# cpu_eval_board.net
KiCad netlist of a schematic drawn in EAGLE
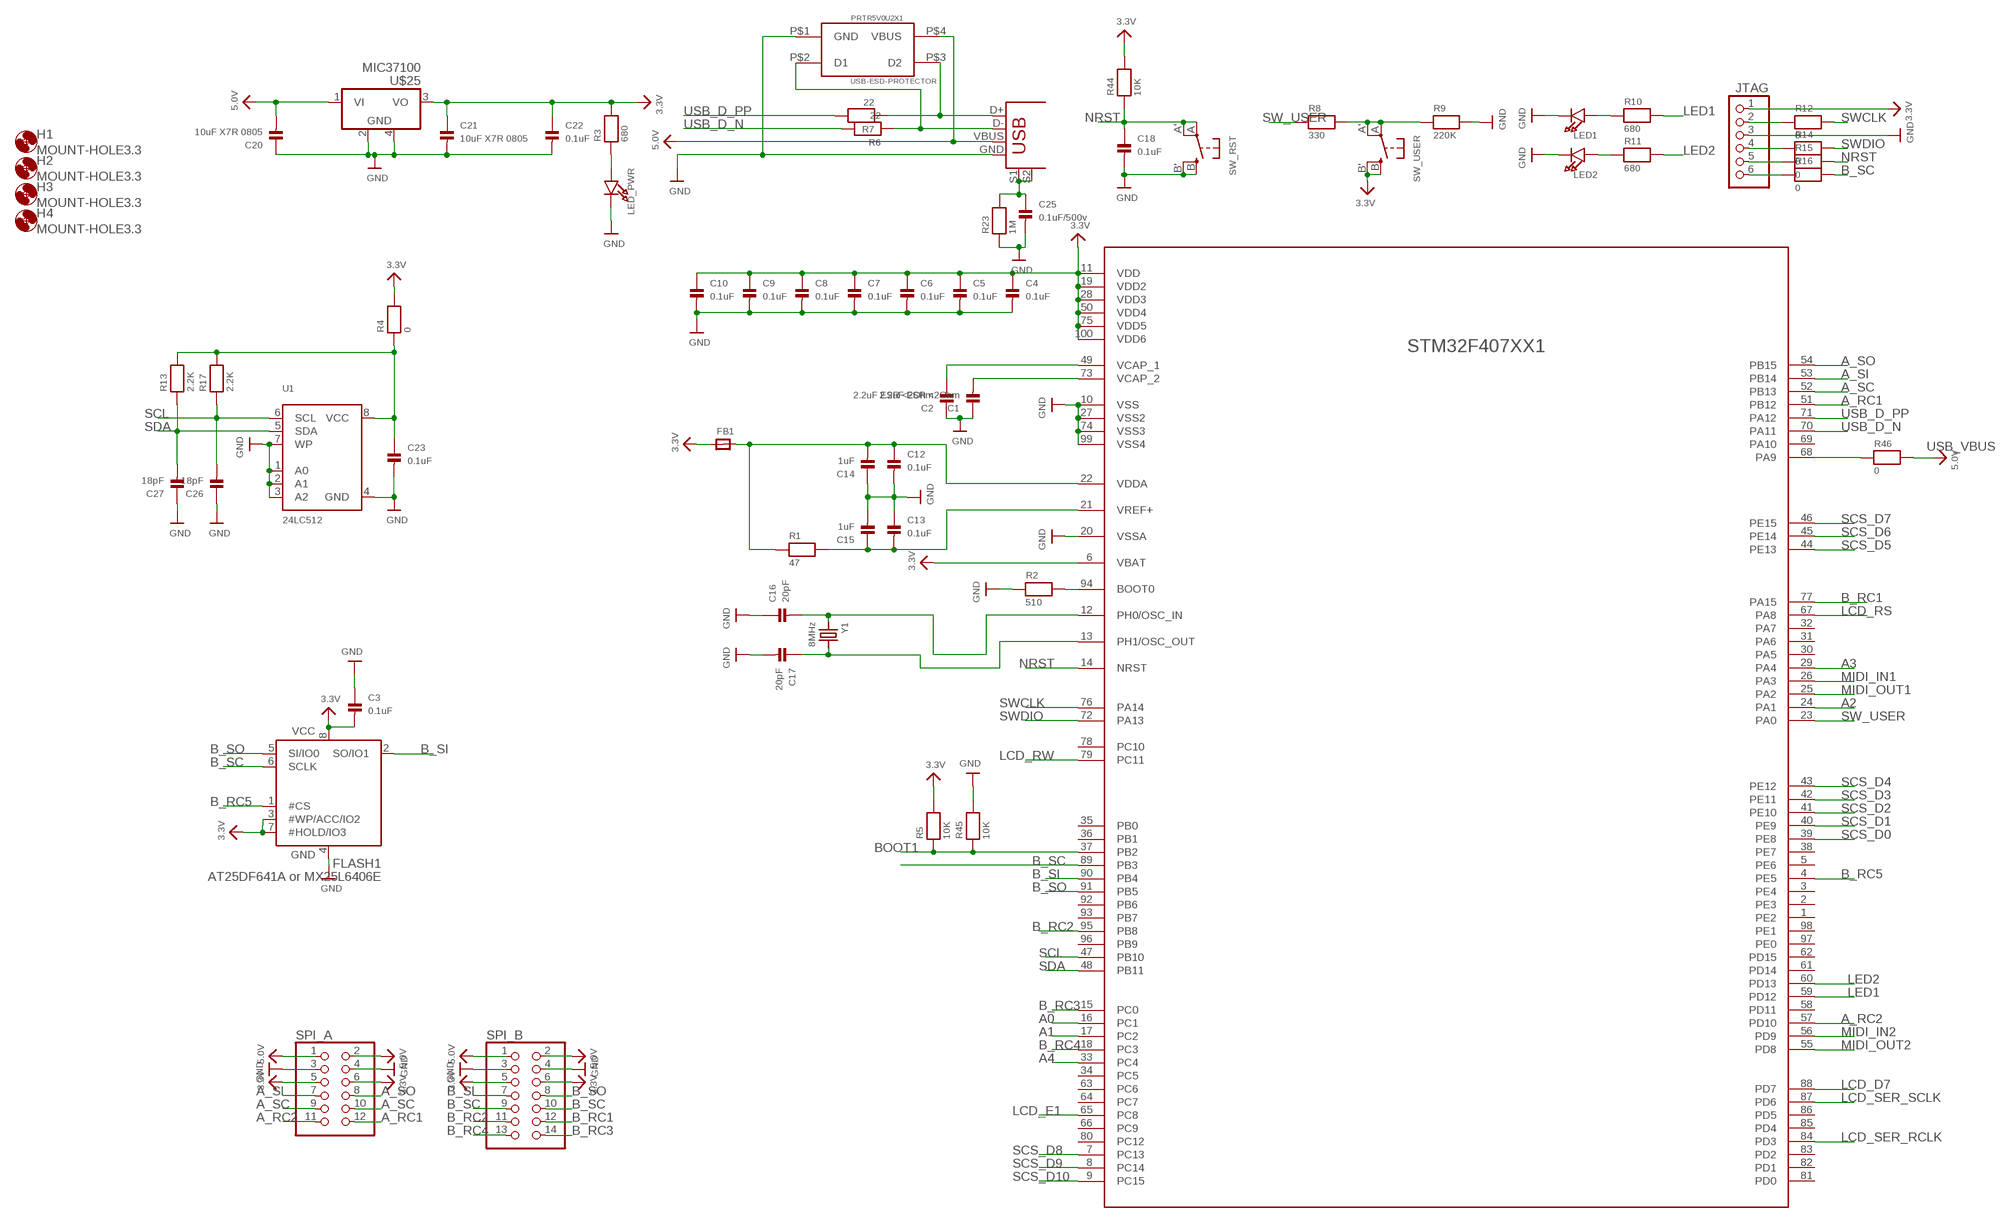
[diagram p0: schematic, sheet 1]
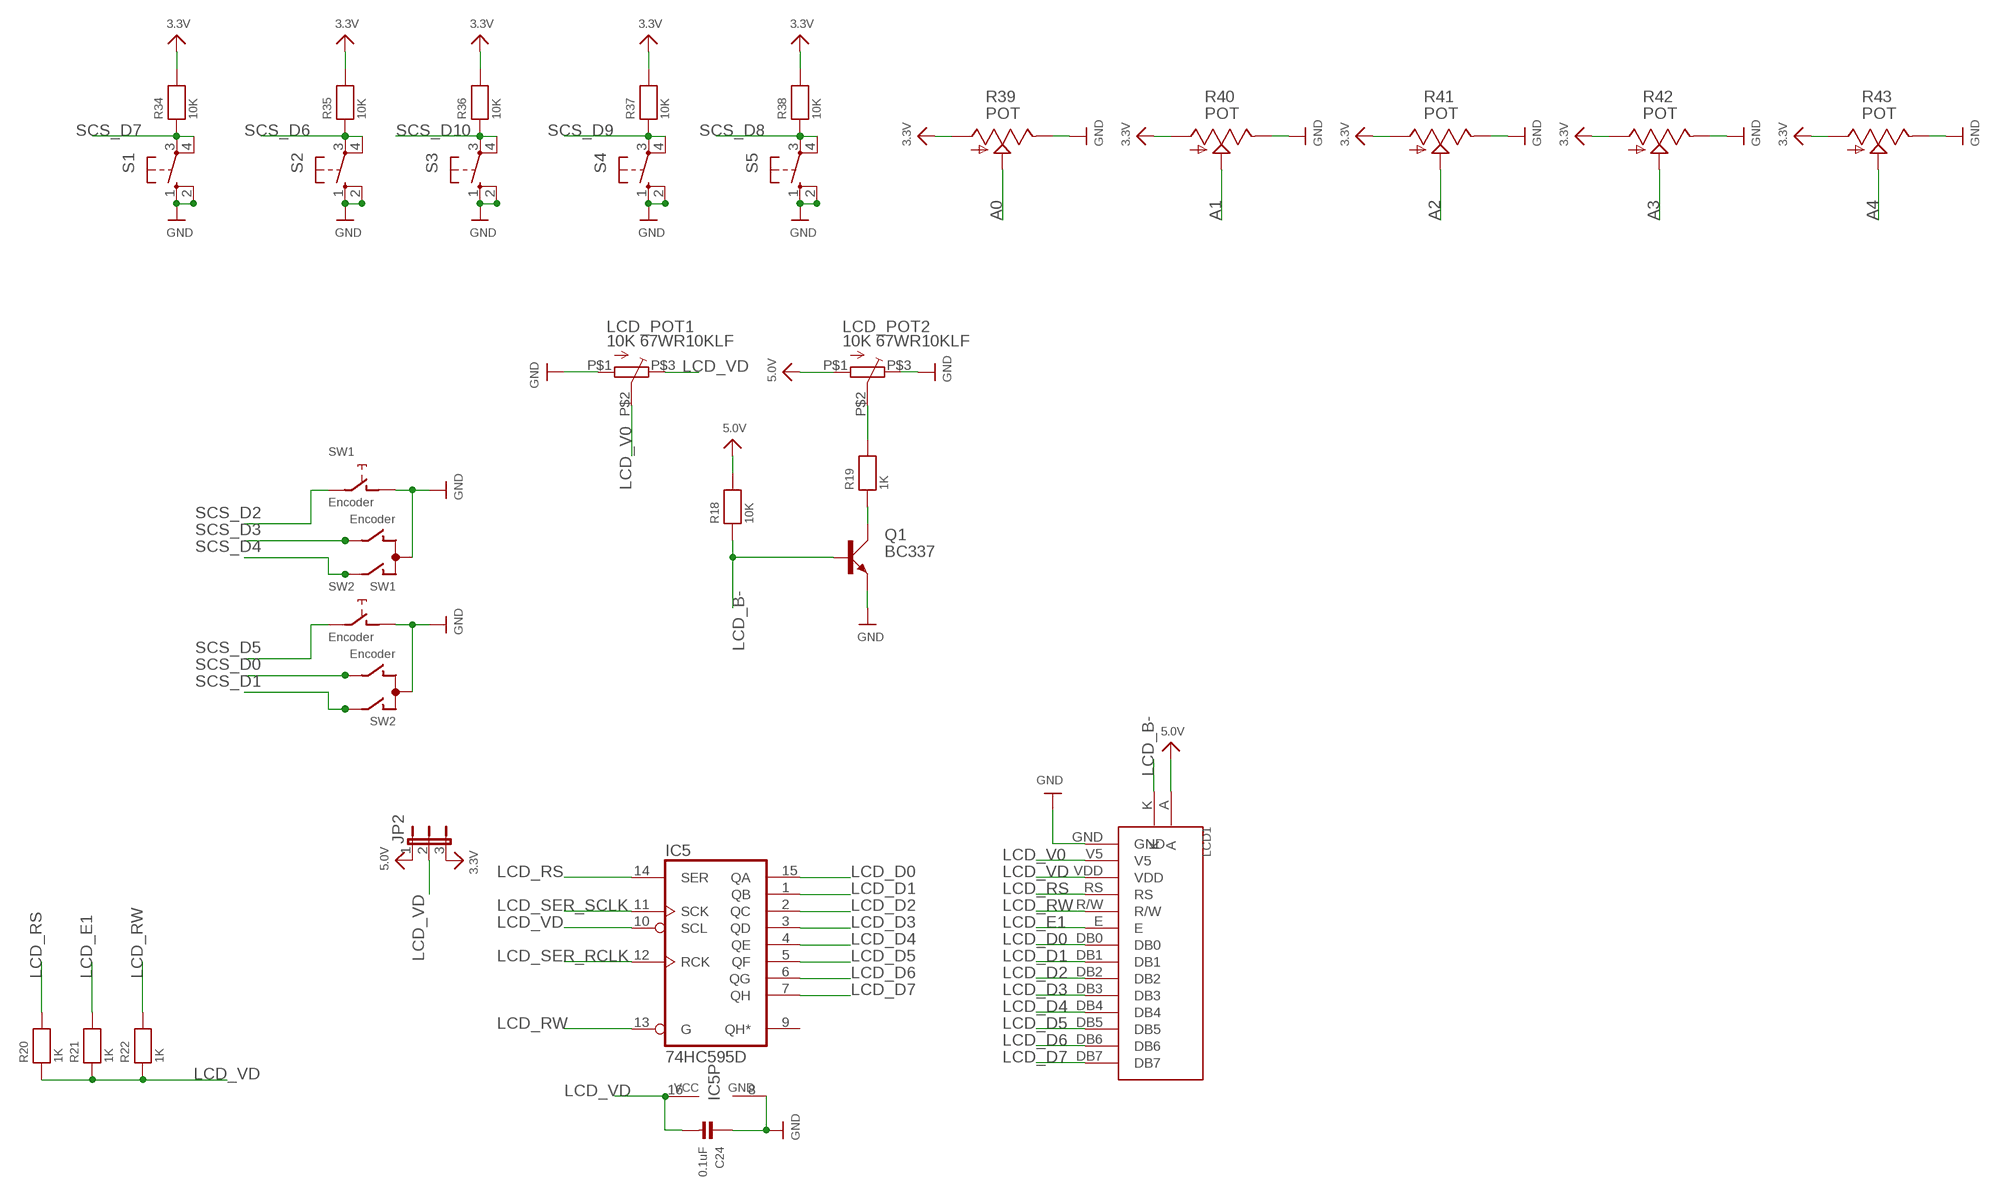
[diagram p1: schematic, sheet 2]
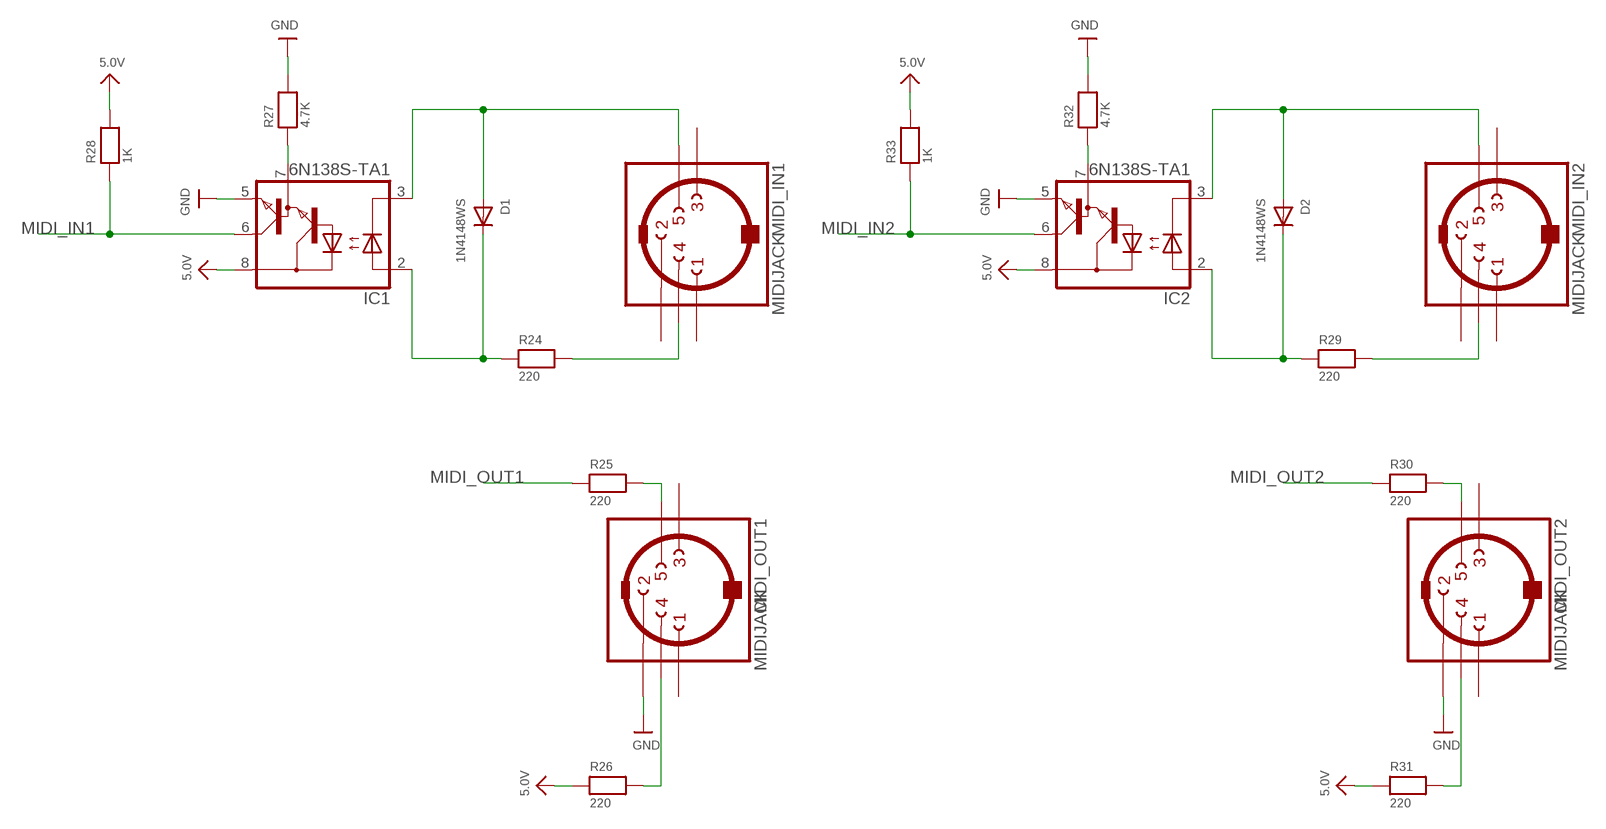
[diagram p2: schematic, sheet 3]

(export (version "E")
  (design (tool "Eeschema 10.0.6"))
  (components
    (comp (ref "D1")
      (value "1N4148WS")
      (footprint "eagle-import:SOD-323")
      (libsource (lib "eagle-import") (part "DIODESOD-323"))
    )
    (comp (ref "D2")
      (value "1N4148WS")
      (footprint "eagle-import:SOD-323")
      (libsource (lib "eagle-import") (part "DIODESOD-323"))
    )
    (comp (ref "IC1")
      (value "6N138S-TA1")
      (footprint "eagle-import:SO8-GW300")
      (libsource (lib "eagle-import") (part "6N138SMD"))
    )
    (comp (ref "IC2")
      (value "6N138S-TA1")
      (footprint "eagle-import:SO8-GW300")
      (libsource (lib "eagle-import") (part "6N138SMD"))
    )
    (comp (ref "MIDI_IN1")
      (value "MIDIJACK")
      (footprint "eagle-import:CP-2350")
      (fields
        (field (name "PARTNO") "57PC5F,Switchcraft,,502-57PC5F,DIN Connectors 5 COND 180 DIN CONN, REF37")
      )
      (libsource (lib "eagle-import") (part "MIDIJACK"))
    )
    (comp (ref "MIDI_IN2")
      (value "MIDIJACK")
      (footprint "eagle-import:CP-2350")
      (fields
        (field (name "PARTNO") "57PC5F,Switchcraft,,502-57PC5F,DIN Connectors 5 COND 180 DIN CONN, REF37")
      )
      (libsource (lib "eagle-import") (part "MIDIJACK"))
    )
    (comp (ref "MIDI_OUT1")
      (value "MIDIJACK")
      (footprint "eagle-import:CP-2350")
      (fields
        (field (name "PARTNO") "57PC5F,Switchcraft,,502-57PC5F,DIN Connectors 5 COND 180 DIN CONN, REF37")
      )
      (libsource (lib "eagle-import") (part "MIDIJACK"))
    )
    (comp (ref "MIDI_OUT2")
      (value "MIDIJACK")
      (footprint "eagle-import:CP-2350")
      (fields
        (field (name "PARTNO") "57PC5F,Switchcraft,,502-57PC5F,DIN Connectors 5 COND 180 DIN CONN, REF37")
      )
      (libsource (lib "eagle-import") (part "MIDIJACK"))
    )
    (comp (ref "R24")
      (value "220")
      (footprint "eagle-import:_0603")
      (libsource (lib "eagle-import") (part "RESISTOR_0603"))
    )
    (comp (ref "R25")
      (value "220")
      (footprint "eagle-import:_0603")
      (libsource (lib "eagle-import") (part "RESISTOR_0603"))
    )
    (comp (ref "R26")
      (value "220")
      (footprint "eagle-import:_0603")
      (libsource (lib "eagle-import") (part "RESISTOR_0603"))
    )
    (comp (ref "R27")
      (value "4.7K")
      (footprint "eagle-import:_0603")
      (libsource (lib "eagle-import") (part "RESISTOR_0603"))
    )
    (comp (ref "R28")
      (value "1K")
      (footprint "eagle-import:_0603")
      (libsource (lib "eagle-import") (part "RESISTOR_0603"))
    )
    (comp (ref "R29")
      (value "220")
      (footprint "eagle-import:_0603")
      (libsource (lib "eagle-import") (part "RESISTOR_0603"))
    )
    (comp (ref "R30")
      (value "220")
      (footprint "eagle-import:_0603")
      (libsource (lib "eagle-import") (part "RESISTOR_0603"))
    )
    (comp (ref "R31")
      (value "220")
      (footprint "eagle-import:_0603")
      (libsource (lib "eagle-import") (part "RESISTOR_0603"))
    )
    (comp (ref "R32")
      (value "4.7K")
      (footprint "eagle-import:_0603")
      (libsource (lib "eagle-import") (part "RESISTOR_0603"))
    )
    (comp (ref "R33")
      (value "1K")
      (footprint "eagle-import:_0603")
      (libsource (lib "eagle-import") (part "RESISTOR_0603"))
    )
    (comp (ref "C24")
      (value "0.1uF")
      (footprint "eagle-import:0603")
      (libsource (lib "eagle-import") (part "CAP_CERAMIC0603"))
    )
    (comp (ref "IC5")
      (value "74HC595D")
      (footprint "eagle-import:SO16")
      (fields
        (field (name "PARTNO") "74HC595D,NXP Semiconductors,,771-74HC595D-T,Counter Shift Registers 8-BIT SHIFT REG W/OUTPUT LATCH, REF12")
      )
      (libsource (lib "eagle-import") (part "74595DHC"))
    )
    (comp (ref "JP2")
      (value "JUMPER3")
      (footprint "eagle-import:JUMPER3")
      (fields
        (field (name "PARTNO") "4-103327-5,TE Connectivity / AMP,,571-4-103327-5,3 pin header 1 row, REF3")
      )
      (libsource (lib "eagle-import") (part "JUMPER3"))
    )
    (comp (ref "LCD1")
      (value "NHD-C0220AA-FSW-FTW")
      (footprint "eagle-import:NHD-C0220AA-FSW-FTW")
      (libsource (lib "eagle-import") (part "NHD-C0220AA-FSW-FTW"))
    )
    (comp (ref "LCD_POT1")
      (value "10K 67WR10KLF")
      (footprint "eagle-import:67W")
      (libsource (lib "eagle-import") (part "TRIMPOT-67W"))
    )
    (comp (ref "LCD_POT2")
      (value "10K 67WR10KLF")
      (footprint "eagle-import:67W")
      (libsource (lib "eagle-import") (part "TRIMPOT-67W"))
    )
    (comp (ref "Q1")
      (value "BC337")
      (footprint "eagle-import:SOT54A")
      (fields
        (field (name "PARTNO") "BC337-16 A1,Taiwan ,,821-BC337-16-A1,Bipolar Transistors - BJT NPN Transistor, REF16")
      )
      (libsource (lib "eagle-import") (part "BC337"))
    )
    (comp (ref "R18")
      (value "10K")
      (footprint "eagle-import:_0603")
      (libsource (lib "eagle-import") (part "RESISTOR_0603"))
    )
    (comp (ref "R19")
      (value "1K")
      (footprint "eagle-import:_0603")
      (libsource (lib "eagle-import") (part "RESISTOR_0603"))
    )
    (comp (ref "R20")
      (value "1K")
      (footprint "eagle-import:_0603")
      (libsource (lib "eagle-import") (part "RESISTOR_0603"))
    )
    (comp (ref "R21")
      (value "1K")
      (footprint "eagle-import:_0603")
      (libsource (lib "eagle-import") (part "RESISTOR_0603"))
    )
    (comp (ref "R22")
      (value "1K")
      (footprint "eagle-import:_0603")
      (libsource (lib "eagle-import") (part "RESISTOR_0603"))
    )
    (comp (ref "R34")
      (value "10K")
      (footprint "eagle-import:_0603")
      (libsource (lib "eagle-import") (part "RESISTOR_0603"))
    )
    (comp (ref "R35")
      (value "10K")
      (footprint "eagle-import:_0603")
      (libsource (lib "eagle-import") (part "RESISTOR_0603"))
    )
    (comp (ref "R36")
      (value "10K")
      (footprint "eagle-import:_0603")
      (libsource (lib "eagle-import") (part "RESISTOR_0603"))
    )
    (comp (ref "R37")
      (value "10K")
      (footprint "eagle-import:_0603")
      (libsource (lib "eagle-import") (part "RESISTOR_0603"))
    )
    (comp (ref "R38")
      (value "10K")
      (footprint "eagle-import:_0603")
      (libsource (lib "eagle-import") (part "RESISTOR_0603"))
    )
    (comp (ref "R39")
      (value "POT")
      (footprint "eagle-import:ALPS_POT_SFE")
      (fields
        (field (name "PARTNO") "RK09D1130C2P,ALPS,,688-RK09D1130C2P,Potentiometers 9MM 10K V/ADJ, REF39")
      )
      (libsource (lib "eagle-import") (part "POT_US"))
    )
    (comp (ref "R40")
      (value "POT")
      (footprint "eagle-import:ALPS_POT_SFE")
      (fields
        (field (name "PARTNO") "RK09D1130C2P,ALPS,,688-RK09D1130C2P,Potentiometers 9MM 10K V/ADJ, REF39")
      )
      (libsource (lib "eagle-import") (part "POT_US"))
    )
    (comp (ref "R41")
      (value "POT")
      (footprint "eagle-import:ALPS_POT_SFE")
      (fields
        (field (name "PARTNO") "RK09D1130C2P,ALPS,,688-RK09D1130C2P,Potentiometers 9MM 10K V/ADJ, REF39")
      )
      (libsource (lib "eagle-import") (part "POT_US"))
    )
    (comp (ref "R42")
      (value "POT")
      (footprint "eagle-import:ALPS_POT_SFE")
      (fields
        (field (name "PARTNO") "RK09D1130C2P,ALPS,,688-RK09D1130C2P,Potentiometers 9MM 10K V/ADJ, REF39")
      )
      (libsource (lib "eagle-import") (part "POT_US"))
    )
    (comp (ref "R43")
      (value "POT")
      (footprint "eagle-import:ALPS_POT_SFE")
      (fields
        (field (name "PARTNO") "RK09D1130C2P,ALPS,,688-RK09D1130C2P,Potentiometers 9MM 10K V/ADJ, REF39")
      )
      (libsource (lib "eagle-import") (part "POT_US"))
    )
    (comp (ref "S1")
      (value "40-XX")
      (footprint "eagle-import:B3F-40XX")
      (fields
        (field (name "PARTNO") "TL1100F160Q,E-Switch,,612-TL1100,Tactile Switches 12X7.3MM 160GF, REF38")
      )
      (libsource (lib "eagle-import") (part "40-XX"))
    )
    (comp (ref "S2")
      (value "40-XX")
      (footprint "eagle-import:B3F-40XX")
      (fields
        (field (name "PARTNO") "TL1100F160Q,E-Switch,,612-TL1100,Tactile Switches 12X7.3MM 160GF, REF38")
      )
      (libsource (lib "eagle-import") (part "40-XX"))
    )
    (comp (ref "S3")
      (value "40-XX")
      (footprint "eagle-import:B3F-40XX")
      (fields
        (field (name "PARTNO") "TL1100F160Q,E-Switch,,612-TL1100,Tactile Switches 12X7.3MM 160GF, REF38")
      )
      (libsource (lib "eagle-import") (part "40-XX"))
    )
    (comp (ref "S4")
      (value "40-XX")
      (footprint "eagle-import:B3F-40XX")
      (fields
        (field (name "PARTNO") "TL1100F160Q,E-Switch,,612-TL1100,Tactile Switches 12X7.3MM 160GF, REF38")
      )
      (libsource (lib "eagle-import") (part "40-XX"))
    )
    (comp (ref "S5")
      (value "40-XX")
      (footprint "eagle-import:B3F-40XX")
      (fields
        (field (name "PARTNO") "TL1100F160Q,E-Switch,,612-TL1100,Tactile Switches 12X7.3MM 160GF, REF38")
      )
      (libsource (lib "eagle-import") (part "40-XX"))
    )
    (comp (ref "SW1")
      (value "Encoder")
      (footprint "eagle-import:ALPS_EC12E_SW")
      (fields
        (field (name "PARTNO") "RK09D1130C2P,ALPS,,688-RK09D1130C2P,Potentiometers 9MM 10K V/ADJ, REF39")
      )
      (libsource (lib "eagle-import") (part "EC12E_SW"))
    )
    (comp (ref "SW2")
      (value "Encoder")
      (footprint "eagle-import:ALPS_EC12E_SW")
      (fields
        (field (name "PARTNO") "RK09D1130C2P,ALPS,,688-RK09D1130C2P,Potentiometers 9MM 10K V/ADJ, REF39")
      )
      (libsource (lib "eagle-import") (part "EC12E_SW"))
    )
    (comp (ref "C1")
      (value "2.2uF ESR <2Ohm")
      (footprint "eagle-import:0603")
      (libsource (lib "eagle-import") (part "CAP_CERAMIC0603"))
    )
    (comp (ref "C2")
      (value "2.2uF ESR <2Ohm")
      (footprint "eagle-import:0603")
      (libsource (lib "eagle-import") (part "CAP_CERAMIC0603"))
    )
    (comp (ref "C3")
      (value "0.1uF")
      (footprint "eagle-import:0603")
      (libsource (lib "eagle-import") (part "CAP_CERAMIC0603"))
    )
    (comp (ref "C4")
      (value "0.1uF")
      (footprint "eagle-import:0603")
      (libsource (lib "eagle-import") (part "CAP_CERAMIC0603"))
    )
    (comp (ref "C5")
      (value "0.1uF")
      (footprint "eagle-import:0603")
      (libsource (lib "eagle-import") (part "CAP_CERAMIC0603"))
    )
    (comp (ref "C6")
      (value "0.1uF")
      (footprint "eagle-import:0603")
      (libsource (lib "eagle-import") (part "CAP_CERAMIC0603"))
    )
    (comp (ref "C7")
      (value "0.1uF")
      (footprint "eagle-import:0603")
      (libsource (lib "eagle-import") (part "CAP_CERAMIC0603"))
    )
    (comp (ref "C8")
      (value "0.1uF")
      (footprint "eagle-import:0603")
      (libsource (lib "eagle-import") (part "CAP_CERAMIC0603"))
    )
    (comp (ref "C9")
      (value "0.1uF")
      (footprint "eagle-import:0603")
      (libsource (lib "eagle-import") (part "CAP_CERAMIC0603"))
    )
    (comp (ref "C10")
      (value "0.1uF")
      (footprint "eagle-import:0603")
      (libsource (lib "eagle-import") (part "CAP_CERAMIC0603"))
    )
    (comp (ref "C12")
      (value "0.1uF")
      (footprint "eagle-import:0603")
      (libsource (lib "eagle-import") (part "CAP_CERAMIC0603"))
    )
    (comp (ref "C13")
      (value "0.1uF")
      (footprint "eagle-import:0603")
      (libsource (lib "eagle-import") (part "CAP_CERAMIC0603"))
    )
    (comp (ref "C14")
      (value "1uF")
      (footprint "eagle-import:0603")
      (libsource (lib "eagle-import") (part "CAP_CERAMIC0603"))
    )
    (comp (ref "C15")
      (value "1uF")
      (footprint "eagle-import:0603")
      (libsource (lib "eagle-import") (part "CAP_CERAMIC0603"))
    )
    (comp (ref "C16")
      (value "20pF")
      (footprint "eagle-import:0603")
      (libsource (lib "eagle-import") (part "CAP_CERAMIC0603"))
    )
    (comp (ref "C17")
      (value "20pF")
      (footprint "eagle-import:0603")
      (libsource (lib "eagle-import") (part "CAP_CERAMIC0603"))
    )
    (comp (ref "C18")
      (value "0.1uF")
      (footprint "eagle-import:0603")
      (libsource (lib "eagle-import") (part "CAP_CERAMIC0603"))
    )
    (comp (ref "C20")
      (value "10uF X7R 0805")
      (footprint "eagle-import:_0805")
      (libsource (lib "eagle-import") (part "CAP_CERAMIC_0805"))
    )
    (comp (ref "C21")
      (value "10uF X7R 0805")
      (footprint "eagle-import:_0805")
      (libsource (lib "eagle-import") (part "CAP_CERAMIC_0805"))
    )
    (comp (ref "C22")
      (value "0.1uF")
      (footprint "eagle-import:0603")
      (libsource (lib "eagle-import") (part "CAP_CERAMIC0603"))
    )
    (comp (ref "C23")
      (value "0.1uF")
      (footprint "eagle-import:0603")
      (libsource (lib "eagle-import") (part "CAP_CERAMIC0603"))
    )
    (comp (ref "C25")
      (value "0.1uF/500v")
      (footprint "eagle-import:0603")
      (libsource (lib "eagle-import") (part "CAP_CERAMIC0603"))
    )
    (comp (ref "C26")
      (value "18pF")
      (footprint "eagle-import:0603")
      (libsource (lib "eagle-import") (part "CAP_CERAMIC0603"))
    )
    (comp (ref "C27")
      (value "18pF")
      (footprint "eagle-import:0603")
      (libsource (lib "eagle-import") (part "CAP_CERAMIC0603"))
    )
    (comp (ref "FB1")
      (value "FERRITE_0805")
      (footprint "eagle-import:_0805")
      (libsource (lib "eagle-import") (part "FERRITE_0805"))
    )
    (comp (ref "FLASH1")
      (value "AT25DF641A or MX25L6406E")
      (footprint "eagle-import:SOIC-8-WIDE")
      (libsource (lib "eagle-import") (part "FLASH-SPI"))
    )
    (comp (ref "H1")
      (value "MOUNT-HOLE3.3")
      (footprint "eagle-import:3,3")
      (libsource (lib "eagle-import") (part "MOUNT-HOLE3.3"))
    )
    (comp (ref "H2")
      (value "MOUNT-HOLE3.3")
      (footprint "eagle-import:3,3")
      (libsource (lib "eagle-import") (part "MOUNT-HOLE3.3"))
    )
    (comp (ref "H3")
      (value "MOUNT-HOLE3.3")
      (footprint "eagle-import:3,3")
      (libsource (lib "eagle-import") (part "MOUNT-HOLE3.3"))
    )
    (comp (ref "H4")
      (value "MOUNT-HOLE3.3")
      (footprint "eagle-import:3,3")
      (libsource (lib "eagle-import") (part "MOUNT-HOLE3.3"))
    )
    (comp (ref "JTAG")
      (value "HEADER-1X6ROUND")
      (footprint "eagle-import:1X06_ROUND")
      (fields (field (name "PARTNO") "XG8V-0641,Omron Electronics,,653-XG8V-0641,6 pin header 1 row, REF2"))
      (libsource (lib "eagle-import") (part "HEADER-1X6ROUND"))
    )
    (comp (ref "LED1")
      (value "LED0603")
      (footprint "eagle-import:CHIPLED_0603")
      (libsource (lib "eagle-import") (part "LED0603"))
    )
    (comp (ref "LED2")
      (value "LED0603")
      (footprint "eagle-import:CHIPLED_0603")
      (libsource (lib "eagle-import") (part "LED0603"))
    )
    (comp (ref "LED_PWR")
      (value "LED0603")
      (footprint "eagle-import:CHIPLED_0603")
      (libsource (lib "eagle-import") (part "LED0603"))
    )
    (comp (ref "PRTR5V0U2X1")
      (value "USB-ESD-PROTECTOR")
      (footprint "eagle-import:PRTR5V0U2X")
      (libsource (lib "eagle-import") (part "USB-ESD-PROTECTOR"))
    )
    (comp (ref "R1")
      (value "47")
      (footprint "eagle-import:0603")
      (libsource (lib "eagle-import") (part "RESISTOR0603"))
    )
    (comp (ref "R2")
      (value "510")
      (footprint "eagle-import:0603")
      (libsource (lib "eagle-import") (part "RESISTOR0603"))
    )
    (comp (ref "R3")
      (value "680")
      (footprint "eagle-import:0603")
      (libsource (lib "eagle-import") (part "RESISTOR0603"))
    )
    (comp (ref "R4")
      (value "0")
      (footprint "eagle-import:0603")
      (libsource (lib "eagle-import") (part "RESISTOR0603"))
    )
    (comp (ref "R5")
      (value "10K")
      (footprint "eagle-import:0603")
      (libsource (lib "eagle-import") (part "RESISTOR0603"))
    )
    (comp (ref "R6")
      (value "22")
      (footprint "eagle-import:0603")
      (libsource (lib "eagle-import") (part "RESISTOR0603"))
    )
    (comp (ref "R7")
      (value "22")
      (footprint "eagle-import:0603")
      (libsource (lib "eagle-import") (part "RESISTOR0603"))
    )
    (comp (ref "R8")
      (value "330")
      (footprint "eagle-import:0603")
      (libsource (lib "eagle-import") (part "RESISTOR0603"))
    )
    (comp (ref "R9")
      (value "220K")
      (footprint "eagle-import:0603")
      (libsource (lib "eagle-import") (part "RESISTOR0603"))
    )
    (comp (ref "R10")
      (value "680")
      (footprint "eagle-import:0603")
      (libsource (lib "eagle-import") (part "RESISTOR0603"))
    )
    (comp (ref "R11")
      (value "680")
      (footprint "eagle-import:0603")
      (libsource (lib "eagle-import") (part "RESISTOR0603"))
    )
    (comp (ref "R12")
      (value "0")
      (footprint "eagle-import:0603")
      (libsource (lib "eagle-import") (part "RESISTOR0603"))
    )
    (comp (ref "R13")
      (value "2.2K")
      (footprint "eagle-import:0603")
      (libsource (lib "eagle-import") (part "RESISTOR0603"))
    )
    (comp (ref "R14")
      (value "0")
      (footprint "eagle-import:0603")
      (libsource (lib "eagle-import") (part "RESISTOR0603"))
    )
    (comp (ref "R15")
      (value "0")
      (footprint "eagle-import:0603")
      (libsource (lib "eagle-import") (part "RESISTOR0603"))
    )
    (comp (ref "R16")
      (value "0")
      (footprint "eagle-import:0603")
      (libsource (lib "eagle-import") (part "RESISTOR0603"))
    )
    (comp (ref "R17")
      (value "2.2K")
      (footprint "eagle-import:0603")
      (libsource (lib "eagle-import") (part "RESISTOR0603"))
    )
    (comp (ref "R23")
      (value "1M")
      (footprint "eagle-import:0603")
      (libsource (lib "eagle-import") (part "RESISTOR0603"))
    )
    (comp (ref "R44")
      (value "10K")
      (footprint "eagle-import:0603")
      (libsource (lib "eagle-import") (part "RESISTOR0603"))
    )
    (comp (ref "R45")
      (value "10K")
      (footprint "eagle-import:0603")
      (libsource (lib "eagle-import") (part "RESISTOR0603"))
    )
    (comp (ref "R46")
      (value "0")
      (footprint "eagle-import:0603")
      (libsource (lib "eagle-import") (part "RESISTOR0603"))
    )
    (comp (ref "SPI_A")
      (value "PINHD-2X6")
      (footprint "eagle-import:2X06")
      (fields (field (name "PARTNO") "67996-412HLF,FCI,,649-67996-412HLF,6x2 header pins, REF4"))
      (libsource (lib "eagle-import") (part "PINHD-2X6"))
    )
    (comp (ref "SPI_B")
      (value "PINHD-2X7")
      (footprint "eagle-import:2X07")
      (fields (field (name "PARTNO") "67997-414HLF,FCI,,649-67997-414HLF,7x2 header pins, REF5"))
      (libsource (lib "eagle-import") (part "PINHD-2X7"))
    )
    (comp (ref "STM32F407XX1")
      (value "STM32F407")
      (footprint "eagle-import:100LQFP")
      (libsource (lib "eagle-import") (part "STM32F407"))
    )
    (comp (ref "SW_RST")
      (value "SWITCH_TACT_SMT")
      (footprint "eagle-import:EVQ-Q2")
      (libsource (lib "eagle-import") (part "SWITCH_TACT_SMT"))
    )
    (comp (ref "SW_USER")
      (value "SWITCH_TACT_SMT")
      (footprint "eagle-import:EVQ-Q2")
      (libsource (lib "eagle-import") (part "SWITCH_TACT_SMT"))
    )
    (comp (ref "U$14")
      (value "Molex 67068-9001")
      (footprint "eagle-import:USB-B-PTH")
      (fields
        (field (name "PARTNO") "67068-9001,Molex,,538-67068-9001,USB Connectors USB Type B Recept R/A w/ Solder Tabs, REF18")
      )
      (libsource (lib "eagle-import") (part "USB+SHIELD"))
    )
    (comp (ref "U$25")
      (value "MIC37100")
      (footprint "eagle-import:SOT223")
      (libsource (lib "eagle-import") (part "MIC37100"))
    )
    (comp (ref "U1")
      (value "24LC512")
      (footprint "eagle-import:SOIC8_150MIL")
      (fields
        (field (name "PARTNO") "24LC512-I/SN,Microchip Technology,,579-24LC512-I/SN,EEPROM 512K 64K X 8 2.5V SER EE IND, REF10")
      )
      (libsource (lib "eagle-import") (part "EEPROM_I2C_SOIC8_GENERIC"))
    )
    (comp (ref "Y1")
      (value "8MHz")
      (footprint "eagle-import:HC49UP")
      (fields
        (field (name "PARTNO") "ABLS-8.000MHZ-B4-T,ABRACON,,815-ABLS-8.0M-T,Crystals 8.000MHz 30ppm -20C +70C 18pF, REF9")
      )
      (libsource (lib "eagle-import") (part "CRYSTALSMD"))
    )
  )
  (nets
    (net (code "1") (name "3.3V") (class "Default")
      (node (ref "C10") (pin "1") (pinfunction "P$1_1") (pintype "passive"))
      (node (ref "C21") (pin "1") (pinfunction "P$1_1") (pintype "passive"))
      (node (ref "C22") (pin "1") (pinfunction "P$1_1") (pintype "passive"))
      (node (ref "C3") (pin "2") (pinfunction "P$2_2") (pintype "passive"))
      (node (ref "C4") (pin "1") (pinfunction "P$1_1") (pintype "passive"))
      (node (ref "C5") (pin "1") (pinfunction "P$1_1") (pintype "passive"))
      (node (ref "C6") (pin "1") (pinfunction "P$1_1") (pintype "passive"))
      (node (ref "C7") (pin "1") (pinfunction "P$1_1") (pintype "passive"))
      (node (ref "C8") (pin "1") (pinfunction "P$1_1") (pintype "passive"))
      (node (ref "C9") (pin "1") (pinfunction "P$1_1") (pintype "passive"))
      (node (ref "FB1") (pin "1") (pinfunction "P$1_1") (pintype "passive"))
      (node (ref "FLASH1") (pin "3") (pinfunction "#WP/ACC/IO2_3") (pintype "bidirectional"))
      (node (ref "FLASH1") (pin "7") (pinfunction "#HOLD/IO3_7") (pintype "bidirectional"))
      (node (ref "FLASH1") (pin "8") (pinfunction "VCC_8") (pintype "power_in"))
      (node (ref "JP2") (pin "3") (pinfunction "3_3") (pintype "passive"))
      (node (ref "JTAG") (pin "1") (pinfunction "1_1") (pintype "passive"))
      (node (ref "R3") (pin "2") (pinfunction "2_2") (pintype "passive"))
      (node (ref "R34") (pin "2") (pinfunction "2_2") (pintype "passive"))
      (node (ref "R35") (pin "2") (pinfunction "2_2") (pintype "passive"))
      (node (ref "R36") (pin "2") (pinfunction "2_2") (pintype "passive"))
      (node (ref "R37") (pin "2") (pinfunction "2_2") (pintype "passive"))
      (node (ref "R38") (pin "2") (pinfunction "2_2") (pintype "passive"))
      (node (ref "R39") (pin "P$3") (pinfunction "A_P$3") (pintype "passive"))
      (node (ref "R4") (pin "2") (pinfunction "2_2") (pintype "passive"))
      (node (ref "R40") (pin "P$3") (pinfunction "A_P$3") (pintype "passive"))
      (node (ref "R41") (pin "P$3") (pinfunction "A_P$3") (pintype "passive"))
      (node (ref "R42") (pin "P$3") (pinfunction "A_P$3") (pintype "passive"))
      (node (ref "R43") (pin "P$3") (pinfunction "A_P$3") (pintype "passive"))
      (node (ref "R44") (pin "2") (pinfunction "2_2") (pintype "passive"))
      (node (ref "R5") (pin "2") (pinfunction "2_2") (pintype "passive"))
      (node (ref "SPI_A") (pin "5") (pinfunction "5_5") (pintype "passive"))
      (node (ref "SPI_A") (pin "6") (pinfunction "6_6") (pintype "passive"))
      (node (ref "SPI_B") (pin "5") (pinfunction "5_5") (pintype "passive"))
      (node (ref "SPI_B") (pin "6") (pinfunction "6_6") (pintype "passive"))
      (node (ref "STM32F407XX1") (pin "100") (pinfunction "VDD6_100") (pintype "bidirectional"))
      (node (ref "STM32F407XX1") (pin "11") (pinfunction "VDD_11") (pintype "bidirectional"))
      (node (ref "STM32F407XX1") (pin "19") (pinfunction "VDD2_19") (pintype "bidirectional"))
      (node (ref "STM32F407XX1") (pin "28") (pinfunction "VDD3_28") (pintype "bidirectional"))
      (node (ref "STM32F407XX1") (pin "50") (pinfunction "VDD4_50") (pintype "bidirectional"))
      (node (ref "STM32F407XX1") (pin "6") (pinfunction "VBAT_6") (pintype "bidirectional"))
      (node (ref "STM32F407XX1") (pin "75") (pinfunction "VDD5_75") (pintype "bidirectional"))
      (node (ref "SW_USER") (pin "B") (pinfunction "S_B") (pintype "passive"))
      (node (ref "SW_USER") (pin "B'") (pinfunction "S1_B'") (pintype "passive"))
      (node (ref "U$25") (pin "3") (pinfunction "VO_3") (pintype "passive"))
    )
    (net (code "2") (name "5.0V") (class "Default")
      (node (ref "C20") (pin "2") (pinfunction "P$2_2") (pintype "passive"))
      (node (ref "IC1") (pin "8") (pinfunction "VCC_8") (pintype "passive"))
      (node (ref "IC2") (pin "8") (pinfunction "VCC_8") (pintype "passive"))
      (node (ref "JP2") (pin "1") (pinfunction "1_1") (pintype "passive"))
      (node (ref "LCD1") (pin "A") (pinfunction "A_A") (pintype "bidirectional"))
      (node (ref "LCD_POT2") (pin "P$1") (pinfunction "A_P$1") (pintype "passive"))
      (node (ref "PRTR5V0U2X1") (pin "P$4") (pinfunction "VBUS_P$4") (pintype "bidirectional"))
      (node (ref "R18") (pin "2") (pinfunction "2_2") (pintype "passive"))
      (node (ref "R26") (pin "1") (pinfunction "1_1") (pintype "passive"))
      (node (ref "R28") (pin "2") (pinfunction "2_2") (pintype "passive"))
      (node (ref "R31") (pin "1") (pinfunction "1_1") (pintype "passive"))
      (node (ref "R33") (pin "2") (pinfunction "2_2") (pintype "passive"))
      (node (ref "R46") (pin "2") (pinfunction "2_2") (pintype "passive"))
      (node (ref "SPI_A") (pin "1") (pinfunction "1_1") (pintype "passive"))
      (node (ref "SPI_A") (pin "2") (pinfunction "2_2") (pintype "passive"))
      (node (ref "SPI_B") (pin "1") (pinfunction "1_1") (pintype "passive"))
      (node (ref "SPI_B") (pin "2") (pinfunction "2_2") (pintype "passive"))
      (node (ref "U$14") (pin "VBUS") (pinfunction "VBUS_VBUS") (pintype "bidirectional"))
      (node (ref "U$25") (pin "1") (pinfunction "VI_1") (pintype "input"))
    )
    (net (code "3") (name "A0") (class "Default")
      (node (ref "R39") (pin "P$2") (pinfunction "S_P$2") (pintype "passive"))
      (node (ref "STM32F407XX1") (pin "16") (pinfunction "PC1_16") (pintype "bidirectional"))
    )
    (net (code "4") (name "A1") (class "Default")
      (node (ref "R40") (pin "P$2") (pinfunction "S_P$2") (pintype "passive"))
      (node (ref "STM32F407XX1") (pin "17") (pinfunction "PC2_17") (pintype "bidirectional"))
    )
    (net (code "5") (name "A2") (class "Default")
      (node (ref "R41") (pin "P$2") (pinfunction "S_P$2") (pintype "passive"))
      (node (ref "STM32F407XX1") (pin "24") (pinfunction "PA1_24") (pintype "bidirectional"))
    )
    (net (code "6") (name "A3") (class "Default")
      (node (ref "R42") (pin "P$2") (pinfunction "S_P$2") (pintype "passive"))
      (node (ref "STM32F407XX1") (pin "29") (pinfunction "PA4_29") (pintype "bidirectional"))
    )
    (net (code "7") (name "A4") (class "Default")
      (node (ref "R43") (pin "P$2") (pinfunction "S_P$2") (pintype "passive"))
      (node (ref "STM32F407XX1") (pin "33") (pinfunction "PC4_33") (pintype "bidirectional"))
    )
    (net (code "8") (name "A_RC1") (class "Default")
      (node (ref "SPI_A") (pin "12") (pinfunction "12_12") (pintype "passive"))
      (node (ref "STM32F407XX1") (pin "51") (pinfunction "PB12_51") (pintype "bidirectional"))
    )
    (net (code "9") (name "A_RC2") (class "Default")
      (node (ref "SPI_A") (pin "11") (pinfunction "11_11") (pintype "passive"))
      (node (ref "STM32F407XX1") (pin "57") (pinfunction "PD10_57") (pintype "bidirectional"))
    )
    (net (code "10") (name "A_SC") (class "Default")
      (node (ref "SPI_A") (pin "10") (pinfunction "10_10") (pintype "passive"))
      (node (ref "SPI_A") (pin "9") (pinfunction "9_9") (pintype "passive"))
      (node (ref "STM32F407XX1") (pin "52") (pinfunction "PB13_52") (pintype "bidirectional"))
    )
    (net (code "11") (name "A_SI") (class "Default")
      (node (ref "SPI_A") (pin "7") (pinfunction "7_7") (pintype "passive"))
      (node (ref "STM32F407XX1") (pin "53") (pinfunction "PB14_53") (pintype "bidirectional"))
    )
    (net (code "12") (name "A_SO") (class "Default")
      (node (ref "SPI_A") (pin "8") (pinfunction "8_8") (pintype "passive"))
      (node (ref "STM32F407XX1") (pin "54") (pinfunction "PB15_54") (pintype "bidirectional"))
    )
    (net (code "13") (name "BOOT1") (class "Default")
      (node (ref "R45") (pin "1") (pinfunction "1_1") (pintype "passive"))
      (node (ref "R5") (pin "1") (pinfunction "1_1") (pintype "passive"))
      (node (ref "STM32F407XX1") (pin "37") (pinfunction "PB2_37") (pintype "bidirectional"))
    )
    (net (code "14") (name "B_RC1") (class "Default")
      (node (ref "SPI_B") (pin "12") (pinfunction "12_12") (pintype "passive"))
      (node (ref "STM32F407XX1") (pin "77") (pinfunction "PA15_77") (pintype "bidirectional"))
    )
    (net (code "15") (name "B_RC2") (class "Default")
      (node (ref "SPI_B") (pin "11") (pinfunction "11_11") (pintype "passive"))
      (node (ref "STM32F407XX1") (pin "95") (pinfunction "PB8_95") (pintype "bidirectional"))
    )
    (net (code "16") (name "B_RC3") (class "Default")
      (node (ref "SPI_B") (pin "14") (pinfunction "14_14") (pintype "passive"))
      (node (ref "STM32F407XX1") (pin "15") (pinfunction "PC0_15") (pintype "bidirectional"))
    )
    (net (code "17") (name "B_RC4") (class "Default")
      (node (ref "SPI_B") (pin "13") (pinfunction "13_13") (pintype "passive"))
      (node (ref "STM32F407XX1") (pin "18") (pinfunction "PC3_18") (pintype "bidirectional"))
    )
    (net (code "18") (name "B_RC5") (class "Default")
      (node (ref "FLASH1") (pin "1") (pinfunction "#CS_1") (pintype "bidirectional"))
      (node (ref "STM32F407XX1") (pin "4") (pinfunction "PE5_4") (pintype "bidirectional"))
    )
    (net (code "19") (name "B_SC") (class "Default")
      (node (ref "FLASH1") (pin "6") (pinfunction "SCLK_6") (pintype "bidirectional"))
      (node (ref "R16") (pin "2") (pinfunction "2_2") (pintype "passive"))
      (node (ref "SPI_B") (pin "10") (pinfunction "10_10") (pintype "passive"))
      (node (ref "SPI_B") (pin "9") (pinfunction "9_9") (pintype "passive"))
      (node (ref "STM32F407XX1") (pin "89") (pinfunction "PB3_89") (pintype "bidirectional"))
    )
    (net (code "20") (name "B_SI") (class "Default")
      (node (ref "FLASH1") (pin "2") (pinfunction "SO/IO1_2") (pintype "bidirectional"))
      (node (ref "SPI_B") (pin "7") (pinfunction "7_7") (pintype "passive"))
      (node (ref "STM32F407XX1") (pin "90") (pinfunction "PB4_90") (pintype "bidirectional"))
    )
    (net (code "21") (name "B_SO") (class "Default")
      (node (ref "FLASH1") (pin "5") (pinfunction "SI/IO0_5") (pintype "bidirectional"))
      (node (ref "SPI_B") (pin "8") (pinfunction "8_8") (pintype "passive"))
      (node (ref "STM32F407XX1") (pin "91") (pinfunction "PB5_91") (pintype "bidirectional"))
    )
    (net (code "22") (name "GND") (class "Default")
      (node (ref "C1") (pin "1") (pinfunction "P$1_1") (pintype "passive"))
      (node (ref "C10") (pin "2") (pinfunction "P$2_2") (pintype "passive"))
      (node (ref "C12") (pin "2") (pinfunction "P$2_2") (pintype "passive"))
      (node (ref "C13") (pin "1") (pinfunction "P$1_1") (pintype "passive"))
      (node (ref "C14") (pin "1") (pinfunction "P$1_1") (pintype "passive"))
      (node (ref "C15") (pin "2") (pinfunction "P$2_2") (pintype "passive"))
      (node (ref "C16") (pin "1") (pinfunction "P$1_1") (pintype "passive"))
      (node (ref "C17") (pin "2") (pinfunction "P$2_2") (pintype "passive"))
      (node (ref "C18") (pin "2") (pinfunction "P$2_2") (pintype "passive"))
      (node (ref "C2") (pin "1") (pinfunction "P$1_1") (pintype "passive"))
      (node (ref "C20") (pin "1") (pinfunction "P$1_1") (pintype "passive"))
      (node (ref "C21") (pin "2") (pinfunction "P$2_2") (pintype "passive"))
      (node (ref "C22") (pin "2") (pinfunction "P$2_2") (pintype "passive"))
      (node (ref "C23") (pin "2") (pinfunction "P$2_2") (pintype "passive"))
      (node (ref "C24") (pin "1") (pinfunction "P$1_1") (pintype "passive"))
      (node (ref "C25") (pin "2") (pinfunction "P$2_2") (pintype "passive"))
      (node (ref "C26") (pin "1") (pinfunction "P$1_1") (pintype "passive"))
      (node (ref "C27") (pin "1") (pinfunction "P$1_1") (pintype "passive"))
      (node (ref "C3") (pin "1") (pinfunction "P$1_1") (pintype "passive"))
      (node (ref "C4") (pin "2") (pinfunction "P$2_2") (pintype "passive"))
      (node (ref "C5") (pin "2") (pinfunction "P$2_2") (pintype "passive"))
      (node (ref "C6") (pin "2") (pinfunction "P$2_2") (pintype "passive"))
      (node (ref "C7") (pin "2") (pinfunction "P$2_2") (pintype "passive"))
      (node (ref "C8") (pin "2") (pinfunction "P$2_2") (pintype "passive"))
      (node (ref "C9") (pin "2") (pinfunction "P$2_2") (pintype "passive"))
      (node (ref "FLASH1") (pin "4") (pinfunction "GND_4") (pintype "power_in"))
      (node (ref "IC1") (pin "5") (pinfunction "GND_5") (pintype "passive"))
      (node (ref "IC2") (pin "5") (pinfunction "GND_5") (pintype "passive"))
      (node (ref "IC5") (pin "8") (pinfunction "GND_8") (pintype "power_in"))
      (node (ref "JTAG") (pin "3") (pinfunction "3_3") (pintype "passive"))
      (node (ref "LCD1") (pin "GND") (pinfunction "GND_GND") (pintype "bidirectional"))
      (node (ref "LCD_POT1") (pin "P$1") (pinfunction "A_P$1") (pintype "passive"))
      (node (ref "LCD_POT2") (pin "P$3") (pinfunction "E_P$3") (pintype "passive"))
      (node (ref "LED1") (pin "C") (pinfunction "C_C") (pintype "passive"))
      (node (ref "LED2") (pin "C") (pinfunction "C_C") (pintype "passive"))
      (node (ref "LED_PWR") (pin "C") (pinfunction "C_C") (pintype "passive"))
      (node (ref "MIDI_OUT1") (pin "2") (pinfunction "2_2") (pintype "passive"))
      (node (ref "MIDI_OUT2") (pin "2") (pinfunction "2_2") (pintype "passive"))
      (node (ref "PRTR5V0U2X1") (pin "P$1") (pinfunction "GND_P$1") (pintype "bidirectional"))
      (node (ref "Q1") (pin "E") (pinfunction "E_E") (pintype "passive"))
      (node (ref "R2") (pin "1") (pinfunction "1_1") (pintype "passive"))
      (node (ref "R23") (pin "1") (pinfunction "1_1") (pintype "passive"))
      (node (ref "R27") (pin "2") (pinfunction "2_2") (pintype "passive"))
      (node (ref "R32") (pin "2") (pinfunction "2_2") (pintype "passive"))
      (node (ref "R39") (pin "P$1") (pinfunction "E_P$1") (pintype "passive"))
      (node (ref "R40") (pin "P$1") (pinfunction "E_P$1") (pintype "passive"))
      (node (ref "R41") (pin "P$1") (pinfunction "E_P$1") (pintype "passive"))
      (node (ref "R42") (pin "P$1") (pinfunction "E_P$1") (pintype "passive"))
      (node (ref "R43") (pin "P$1") (pinfunction "E_P$1") (pintype "passive"))
      (node (ref "R45") (pin "2") (pinfunction "2_2") (pintype "passive"))
      (node (ref "R9") (pin "2") (pinfunction "2_2") (pintype "passive"))
      (node (ref "S1") (pin "1") (pinfunction "S_1") (pintype "passive"))
      (node (ref "S1") (pin "2") (pinfunction "S1_2") (pintype "passive"))
      (node (ref "S2") (pin "1") (pinfunction "S_1") (pintype "passive"))
      (node (ref "S2") (pin "2") (pinfunction "S1_2") (pintype "passive"))
      (node (ref "S3") (pin "1") (pinfunction "S_1") (pintype "passive"))
      (node (ref "S3") (pin "2") (pinfunction "S1_2") (pintype "passive"))
      (node (ref "S4") (pin "1") (pinfunction "S_1") (pintype "passive"))
      (node (ref "S4") (pin "2") (pinfunction "S1_2") (pintype "passive"))
      (node (ref "S5") (pin "1") (pinfunction "S_1") (pintype "passive"))
      (node (ref "S5") (pin "2") (pinfunction "S1_2") (pintype "passive"))
      (node (ref "SPI_A") (pin "3") (pinfunction "3_3") (pintype "passive"))
      (node (ref "SPI_A") (pin "4") (pinfunction "4_4") (pintype "passive"))
      (node (ref "SPI_B") (pin "3") (pinfunction "3_3") (pintype "passive"))
      (node (ref "SPI_B") (pin "4") (pinfunction "4_4") (pintype "passive"))
      (node (ref "STM32F407XX1") (pin "10") (pinfunction "VSS_10") (pintype "bidirectional"))
      (node (ref "STM32F407XX1") (pin "20") (pinfunction "VSSA_20") (pintype "bidirectional"))
      (node (ref "STM32F407XX1") (pin "27") (pinfunction "VSS2_27") (pintype "bidirectional"))
      (node (ref "STM32F407XX1") (pin "74") (pinfunction "VSS3_74") (pintype "bidirectional"))
      (node (ref "STM32F407XX1") (pin "99") (pinfunction "VSS4_99") (pintype "bidirectional"))
      (node (ref "SW1") (pin "C") (pinfunction "C_C") (pintype "passive"))
      (node (ref "SW1") (pin "D") (pinfunction "1_D") (pintype "passive"))
      (node (ref "SW2") (pin "C") (pinfunction "C_C") (pintype "passive"))
      (node (ref "SW2") (pin "D") (pinfunction "1_D") (pintype "passive"))
      (node (ref "SW_RST") (pin "B") (pinfunction "S_B") (pintype "passive"))
      (node (ref "SW_RST") (pin "B'") (pinfunction "S1_B'") (pintype "passive"))
      (node (ref "U$14") (pin "GND") (pinfunction "GND_GND") (pintype "bidirectional"))
      (node (ref "U$25") (pin "2") (pinfunction "GND_2") (pintype "passive"))
      (node (ref "U$25") (pin "4") (pinfunction "GND_TAB_4") (pintype "passive"))
      (node (ref "U1") (pin "1") (pinfunction "A0_1") (pintype "input"))
      (node (ref "U1") (pin "2") (pinfunction "A1_2") (pintype "input"))
      (node (ref "U1") (pin "3") (pinfunction "A2_3") (pintype "input"))
      (node (ref "U1") (pin "4") (pinfunction "GND_4") (pintype "power_in"))
      (node (ref "U1") (pin "7") (pinfunction "WP_7") (pintype "input"))
    )
    (net (code "23") (name "LCD_B-") (class "Default")
      (node (ref "LCD1") (pin "K") (pinfunction "K_K") (pintype "bidirectional"))
      (node (ref "Q1") (pin "B") (pinfunction "B_B") (pintype "passive"))
      (node (ref "R18") (pin "1") (pinfunction "1_1") (pintype "passive"))
    )
    (net (code "24") (name "LCD_D0") (class "Default")
      (node (ref "IC5") (pin "15") (pinfunction "QA_15") (pintype "tri_state"))
      (node (ref "LCD1") (pin "DB0") (pinfunction "DB0_DB0") (pintype "bidirectional"))
    )
    (net (code "25") (name "LCD_D1") (class "Default")
      (node (ref "IC5") (pin "1") (pinfunction "QB_1") (pintype "tri_state"))
      (node (ref "LCD1") (pin "DB1") (pinfunction "DB1_DB1") (pintype "bidirectional"))
    )
    (net (code "26") (name "LCD_D2") (class "Default")
      (node (ref "IC5") (pin "2") (pinfunction "QC_2") (pintype "tri_state"))
      (node (ref "LCD1") (pin "DB2") (pinfunction "DB2_DB2") (pintype "bidirectional"))
    )
    (net (code "27") (name "LCD_D3") (class "Default")
      (node (ref "IC5") (pin "3") (pinfunction "QD_3") (pintype "tri_state"))
      (node (ref "LCD1") (pin "DB3") (pinfunction "DB3_DB3") (pintype "bidirectional"))
    )
    (net (code "28") (name "LCD_D4") (class "Default")
      (node (ref "IC5") (pin "4") (pinfunction "QE_4") (pintype "tri_state"))
      (node (ref "LCD1") (pin "DB4") (pinfunction "DB4_DB4") (pintype "bidirectional"))
    )
    (net (code "29") (name "LCD_D5") (class "Default")
      (node (ref "IC5") (pin "5") (pinfunction "QF_5") (pintype "tri_state"))
      (node (ref "LCD1") (pin "DB5") (pinfunction "DB5_DB5") (pintype "bidirectional"))
    )
    (net (code "30") (name "LCD_D6") (class "Default")
      (node (ref "IC5") (pin "6") (pinfunction "QG_6") (pintype "tri_state"))
      (node (ref "LCD1") (pin "DB6") (pinfunction "DB6_DB6") (pintype "bidirectional"))
    )
    (net (code "31") (name "LCD_D7") (class "Default")
      (node (ref "IC5") (pin "7") (pinfunction "QH_7") (pintype "tri_state"))
      (node (ref "LCD1") (pin "DB7") (pinfunction "DB7_DB7") (pintype "bidirectional"))
      (node (ref "STM32F407XX1") (pin "88") (pinfunction "PD7_88") (pintype "bidirectional"))
    )
    (net (code "32") (name "LCD_E1") (class "Default")
      (node (ref "LCD1") (pin "E") (pinfunction "E_E") (pintype "bidirectional"))
      (node (ref "R21") (pin "2") (pinfunction "2_2") (pintype "passive"))
      (node (ref "STM32F407XX1") (pin "65") (pinfunction "PC8_65") (pintype "bidirectional"))
    )
    (net (code "33") (name "LCD_RS") (class "Default")
      (node (ref "IC5") (pin "14") (pinfunction "SER_14") (pintype "input"))
      (node (ref "LCD1") (pin "RS") (pinfunction "RS_RS") (pintype "bidirectional"))
      (node (ref "R20") (pin "2") (pinfunction "2_2") (pintype "passive"))
      (node (ref "STM32F407XX1") (pin "67") (pinfunction "PA8_67") (pintype "bidirectional"))
    )
    (net (code "34") (name "LCD_RW") (class "Default")
      (node (ref "IC5") (pin "13") (pinfunction "G_13") (pintype "input"))
      (node (ref "LCD1") (pin "R/W") (pinfunction "R/W_R/W") (pintype "bidirectional"))
      (node (ref "R22") (pin "2") (pinfunction "2_2") (pintype "passive"))
      (node (ref "STM32F407XX1") (pin "79") (pinfunction "PC11_79") (pintype "bidirectional"))
    )
    (net (code "35") (name "LCD_SER_RCLK") (class "Default")
      (node (ref "IC5") (pin "12") (pinfunction "RCK_12") (pintype "input"))
      (node (ref "STM32F407XX1") (pin "84") (pinfunction "PD3_84") (pintype "bidirectional"))
    )
    (net (code "36") (name "LCD_SER_SCLK") (class "Default")
      (node (ref "IC5") (pin "11") (pinfunction "SCK_11") (pintype "input"))
      (node (ref "STM32F407XX1") (pin "87") (pinfunction "PD6_87") (pintype "bidirectional"))
    )
    (net (code "37") (name "LCD_V0") (class "Default")
      (node (ref "LCD1") (pin "V5") (pinfunction "V5_V5") (pintype "bidirectional"))
      (node (ref "LCD_POT1") (pin "P$2") (pinfunction "S_P$2") (pintype "passive"))
    )
    (net (code "38") (name "LCD_VD") (class "Default")
      (node (ref "C24") (pin "2") (pinfunction "P$2_2") (pintype "passive"))
      (node (ref "IC5") (pin "10") (pinfunction "SCL_10") (pintype "input"))
      (node (ref "IC5") (pin "16") (pinfunction "VCC_16") (pintype "power_in"))
      (node (ref "JP2") (pin "2") (pinfunction "2_2") (pintype "passive"))
      (node (ref "LCD1") (pin "VDD") (pinfunction "VDD_VDD") (pintype "bidirectional"))
      (node (ref "LCD_POT1") (pin "P$3") (pinfunction "E_P$3") (pintype "passive"))
      (node (ref "R20") (pin "1") (pinfunction "1_1") (pintype "passive"))
      (node (ref "R21") (pin "1") (pinfunction "1_1") (pintype "passive"))
      (node (ref "R22") (pin "1") (pinfunction "1_1") (pintype "passive"))
    )
    (net (code "39") (name "LED1") (class "Default")
      (node (ref "R10") (pin "2") (pinfunction "2_2") (pintype "passive"))
      (node (ref "STM32F407XX1") (pin "59") (pinfunction "PD12_59") (pintype "bidirectional"))
    )
    (net (code "40") (name "LED2") (class "Default")
      (node (ref "R11") (pin "2") (pinfunction "2_2") (pintype "passive"))
      (node (ref "STM32F407XX1") (pin "60") (pinfunction "PD13_60") (pintype "bidirectional"))
    )
    (net (code "41") (name "MIDI_IN1") (class "Default")
      (node (ref "IC1") (pin "6") (pinfunction "VO_6") (pintype "passive"))
      (node (ref "R28") (pin "1") (pinfunction "1_1") (pintype "passive"))
      (node (ref "STM32F407XX1") (pin "26") (pinfunction "PA3_26") (pintype "bidirectional"))
    )
    (net (code "42") (name "MIDI_IN2") (class "Default")
      (node (ref "IC2") (pin "6") (pinfunction "VO_6") (pintype "passive"))
      (node (ref "R33") (pin "1") (pinfunction "1_1") (pintype "passive"))
      (node (ref "STM32F407XX1") (pin "56") (pinfunction "PD9_56") (pintype "bidirectional"))
    )
    (net (code "43") (name "MIDI_OUT1") (class "Default")
      (node (ref "R25") (pin "1") (pinfunction "1_1") (pintype "passive"))
      (node (ref "STM32F407XX1") (pin "25") (pinfunction "PA2_25") (pintype "bidirectional"))
    )
    (net (code "44") (name "MIDI_OUT2") (class "Default")
      (node (ref "R30") (pin "1") (pinfunction "1_1") (pintype "passive"))
      (node (ref "STM32F407XX1") (pin "55") (pinfunction "PD8_55") (pintype "bidirectional"))
    )
    (net (code "45") (name "NRST") (class "Default")
      (node (ref "C18") (pin "1") (pinfunction "P$1_1") (pintype "passive"))
      (node (ref "R15") (pin "2") (pinfunction "2_2") (pintype "passive"))
      (node (ref "R44") (pin "1") (pinfunction "1_1") (pintype "passive"))
      (node (ref "STM32F407XX1") (pin "14") (pinfunction "NRST_14") (pintype "bidirectional"))
      (node (ref "SW_RST") (pin "A") (pinfunction "P_A") (pintype "passive"))
      (node (ref "SW_RST") (pin "A'") (pinfunction "P1_A'") (pintype "passive"))
    )
    (net (code "46") (name "Net-(C1-P$2)") (class "Default")
      (node (ref "C1") (pin "2") (pinfunction "P$2_2") (pintype "passive"))
      (node (ref "STM32F407XX1") (pin "73") (pinfunction "VCAP_2_73") (pintype "bidirectional"))
    )
    (net (code "47") (name "Net-(C2-P$2)") (class "Default")
      (node (ref "C2") (pin "2") (pinfunction "P$2_2") (pintype "passive"))
      (node (ref "STM32F407XX1") (pin "49") (pinfunction "VCAP_1_49") (pintype "bidirectional"))
    )
    (net (code "48") (name "Net-(C12-P$1)") (class "Default")
      (node (ref "C12") (pin "1") (pinfunction "P$1_1") (pintype "passive"))
      (node (ref "C14") (pin "2") (pinfunction "P$2_2") (pintype "passive"))
      (node (ref "FB1") (pin "2") (pinfunction "P$2_2") (pintype "passive"))
      (node (ref "R1") (pin "1") (pinfunction "1_1") (pintype "passive"))
      (node (ref "STM32F407XX1") (pin "22") (pinfunction "VDDA_22") (pintype "bidirectional"))
    )
    (net (code "49") (name "Net-(C13-P$2)") (class "Default")
      (node (ref "C13") (pin "2") (pinfunction "P$2_2") (pintype "passive"))
      (node (ref "C15") (pin "1") (pinfunction "P$1_1") (pintype "passive"))
      (node (ref "R1") (pin "2") (pinfunction "2_2") (pintype "passive"))
      (node (ref "STM32F407XX1") (pin "21") (pinfunction "VREF+_21") (pintype "bidirectional"))
    )
    (net (code "50") (name "Net-(C16-P$2)") (class "Default")
      (node (ref "C16") (pin "2") (pinfunction "P$2_2") (pintype "passive"))
      (node (ref "STM32F407XX1") (pin "12") (pinfunction "PH0/OSC_IN_12") (pintype "bidirectional"))
      (node (ref "Y1") (pin "1") (pinfunction "1_1") (pintype "passive"))
    )
    (net (code "51") (name "Net-(C17-P$1)") (class "Default")
      (node (ref "C17") (pin "1") (pinfunction "P$1_1") (pintype "passive"))
      (node (ref "STM32F407XX1") (pin "13") (pinfunction "PH1/OSC_OUT_13") (pintype "bidirectional"))
      (node (ref "Y1") (pin "2") (pinfunction "2_2") (pintype "passive"))
    )
    (net (code "52") (name "Net-(C23-P$1)") (class "Default")
      (node (ref "C23") (pin "1") (pinfunction "P$1_1") (pintype "passive"))
      (node (ref "R13") (pin "2") (pinfunction "2_2") (pintype "passive"))
      (node (ref "R17") (pin "2") (pinfunction "2_2") (pintype "passive"))
      (node (ref "R4") (pin "1") (pinfunction "1_1") (pintype "passive"))
      (node (ref "U1") (pin "8") (pinfunction "VCC_8") (pintype "power_in"))
    )
    (net (code "53") (name "Net-(C25-P$1)") (class "Default")
      (node (ref "C25") (pin "1") (pinfunction "P$1_1") (pintype "passive"))
      (node (ref "R23") (pin "2") (pinfunction "2_2") (pintype "passive"))
      (node (ref "U$14") (pin "S1") (pinfunction "S1_S1") (pintype "bidirectional"))
      (node (ref "U$14") (pin "S2") (pinfunction "S2_S2") (pintype "bidirectional"))
    )
    (net (code "54") (name "Net-(IC1-A)") (class "Default")
      (node (ref "D1") (pin "C") (pinfunction "C_C") (pintype "passive"))
      (node (ref "IC1") (pin "2") (pinfunction "A_2") (pintype "passive"))
      (node (ref "R24") (pin "1") (pinfunction "1_1") (pintype "passive"))
    )
    (net (code "55") (name "Net-(IC1-C)") (class "Default")
      (node (ref "D1") (pin "A") (pinfunction "A_A") (pintype "passive"))
      (node (ref "IC1") (pin "3") (pinfunction "C_3") (pintype "passive"))
      (node (ref "MIDI_IN1") (pin "5") (pinfunction "5_5") (pintype "passive"))
    )
    (net (code "56") (name "Net-(IC1-VB)") (class "Default")
      (node (ref "IC1") (pin "7") (pinfunction "VB_7") (pintype "passive"))
      (node (ref "R27") (pin "1") (pinfunction "1_1") (pintype "passive"))
    )
    (net (code "57") (name "Net-(IC2-A)") (class "Default")
      (node (ref "D2") (pin "C") (pinfunction "C_C") (pintype "passive"))
      (node (ref "IC2") (pin "2") (pinfunction "A_2") (pintype "passive"))
      (node (ref "R29") (pin "1") (pinfunction "1_1") (pintype "passive"))
    )
    (net (code "58") (name "Net-(IC2-C)") (class "Default")
      (node (ref "D2") (pin "A") (pinfunction "A_A") (pintype "passive"))
      (node (ref "IC2") (pin "3") (pinfunction "C_3") (pintype "passive"))
      (node (ref "MIDI_IN2") (pin "5") (pinfunction "5_5") (pintype "passive"))
    )
    (net (code "59") (name "Net-(IC2-VB)") (class "Default")
      (node (ref "IC2") (pin "7") (pinfunction "VB_7") (pintype "passive"))
      (node (ref "R32") (pin "1") (pinfunction "1_1") (pintype "passive"))
    )
    (net (code "60") (name "Net-(JTAG-Pad2)") (class "Default")
      (node (ref "JTAG") (pin "2") (pinfunction "2_2") (pintype "passive"))
      (node (ref "R12") (pin "1") (pinfunction "1_1") (pintype "passive"))
    )
    (net (code "61") (name "Net-(JTAG-Pad4)") (class "Default")
      (node (ref "JTAG") (pin "4") (pinfunction "4_4") (pintype "passive"))
      (node (ref "R14") (pin "1") (pinfunction "1_1") (pintype "passive"))
    )
    (net (code "62") (name "Net-(JTAG-Pad5)") (class "Default")
      (node (ref "JTAG") (pin "5") (pinfunction "5_5") (pintype "passive"))
      (node (ref "R15") (pin "1") (pinfunction "1_1") (pintype "passive"))
    )
    (net (code "63") (name "Net-(JTAG-Pad6)") (class "Default")
      (node (ref "JTAG") (pin "6") (pinfunction "6_6") (pintype "passive"))
      (node (ref "R16") (pin "1") (pinfunction "1_1") (pintype "passive"))
    )
    (net (code "64") (name "Net-(LCD_POT2-S)") (class "Default")
      (node (ref "LCD_POT2") (pin "P$2") (pinfunction "S_P$2") (pintype "passive"))
      (node (ref "R19") (pin "2") (pinfunction "2_2") (pintype "passive"))
    )
    (net (code "65") (name "Net-(LED1-PadA)") (class "Default")
      (node (ref "LED1") (pin "A") (pinfunction "A_A") (pintype "passive"))
      (node (ref "R10") (pin "1") (pinfunction "1_1") (pintype "passive"))
    )
    (net (code "66") (name "Net-(LED2-PadA)") (class "Default")
      (node (ref "LED2") (pin "A") (pinfunction "A_A") (pintype "passive"))
      (node (ref "R11") (pin "1") (pinfunction "1_1") (pintype "passive"))
    )
    (net (code "67") (name "Net-(LED_PWR-PadA)") (class "Default")
      (node (ref "LED_PWR") (pin "A") (pinfunction "A_A") (pintype "passive"))
      (node (ref "R3") (pin "1") (pinfunction "1_1") (pintype "passive"))
    )
    (net (code "68") (name "Net-(MIDI_IN1-Pad4)") (class "Default")
      (node (ref "MIDI_IN1") (pin "4") (pinfunction "4_4") (pintype "passive"))
      (node (ref "R24") (pin "2") (pinfunction "2_2") (pintype "passive"))
    )
    (net (code "69") (name "Net-(MIDI_IN2-Pad4)") (class "Default")
      (node (ref "MIDI_IN2") (pin "4") (pinfunction "4_4") (pintype "passive"))
      (node (ref "R29") (pin "2") (pinfunction "2_2") (pintype "passive"))
    )
    (net (code "70") (name "Net-(MIDI_OUT1-Pad4)") (class "Default")
      (node (ref "MIDI_OUT1") (pin "4") (pinfunction "4_4") (pintype "passive"))
      (node (ref "R26") (pin "2") (pinfunction "2_2") (pintype "passive"))
    )
    (net (code "71") (name "Net-(MIDI_OUT1-Pad5)") (class "Default")
      (node (ref "MIDI_OUT1") (pin "5") (pinfunction "5_5") (pintype "passive"))
      (node (ref "R25") (pin "2") (pinfunction "2_2") (pintype "passive"))
    )
    (net (code "72") (name "Net-(MIDI_OUT2-Pad4)") (class "Default")
      (node (ref "MIDI_OUT2") (pin "4") (pinfunction "4_4") (pintype "passive"))
      (node (ref "R31") (pin "2") (pinfunction "2_2") (pintype "passive"))
    )
    (net (code "73") (name "Net-(MIDI_OUT2-Pad5)") (class "Default")
      (node (ref "MIDI_OUT2") (pin "5") (pinfunction "5_5") (pintype "passive"))
      (node (ref "R30") (pin "2") (pinfunction "2_2") (pintype "passive"))
    )
    (net (code "74") (name "Net-(PRTR5V0U2X1-D1)") (class "Default")
      (node (ref "PRTR5V0U2X1") (pin "P$2") (pinfunction "D1_P$2") (pintype "bidirectional"))
      (node (ref "R6") (pin "1") (pinfunction "1_1") (pintype "passive"))
      (node (ref "U$14") (pin "D-") (pinfunction "D-_D-") (pintype "bidirectional"))
    )
    (net (code "75") (name "Net-(PRTR5V0U2X1-D2)") (class "Default")
      (node (ref "PRTR5V0U2X1") (pin "P$3") (pinfunction "D2_P$3") (pintype "bidirectional"))
      (node (ref "R7") (pin "1") (pinfunction "1_1") (pintype "passive"))
      (node (ref "U$14") (pin "D+") (pinfunction "D+_D+") (pintype "bidirectional"))
    )
    (net (code "76") (name "Net-(Q1-PadC)") (class "Default")
      (node (ref "Q1") (pin "C") (pinfunction "C_C") (pintype "passive"))
      (node (ref "R19") (pin "1") (pinfunction "1_1") (pintype "passive"))
    )
    (net (code "77") (name "Net-(STM32F407XX1-BOOT0)") (class "Default")
      (node (ref "R2") (pin "2") (pinfunction "2_2") (pintype "passive"))
      (node (ref "STM32F407XX1") (pin "94") (pinfunction "BOOT0_94") (pintype "bidirectional"))
    )
    (net (code "78") (name "Net-(STM32F407XX1-PA9)") (class "Default")
      (node (ref "R46") (pin "1") (pinfunction "1_1") (pintype "passive"))
      (node (ref "STM32F407XX1") (pin "68") (pinfunction "PA9_68") (pintype "bidirectional"))
    )
    (net (code "79") (name "Net-(SW_USER-P)") (class "Default")
      (node (ref "R8") (pin "2") (pinfunction "2_2") (pintype "passive"))
      (node (ref "R9") (pin "1") (pinfunction "1_1") (pintype "passive"))
      (node (ref "SW_USER") (pin "A") (pinfunction "P_A") (pintype "passive"))
      (node (ref "SW_USER") (pin "A'") (pinfunction "P1_A'") (pintype "passive"))
    )
    (net (code "80") (name "SCL") (class "Default")
      (node (ref "C26") (pin "2") (pinfunction "P$2_2") (pintype "passive"))
      (node (ref "R17") (pin "1") (pinfunction "1_1") (pintype "passive"))
      (node (ref "STM32F407XX1") (pin "47") (pinfunction "PB10_47") (pintype "bidirectional"))
      (node (ref "U1") (pin "6") (pinfunction "SCL_6") (pintype "input"))
    )
    (net (code "81") (name "SCS_D0") (class "Default")
      (node (ref "STM32F407XX1") (pin "39") (pinfunction "PE8_39") (pintype "bidirectional"))
      (node (ref "SW2") (pin "B") (pinfunction "B_B") (pintype "passive"))
    )
    (net (code "82") (name "SCS_D1") (class "Default")
      (node (ref "STM32F407XX1") (pin "40") (pinfunction "PE9_40") (pintype "bidirectional"))
      (node (ref "SW2") (pin "A") (pinfunction "A_A") (pintype "passive"))
    )
    (net (code "83") (name "SCS_D2") (class "Default")
      (node (ref "STM32F407XX1") (pin "41") (pinfunction "PE10_41") (pintype "bidirectional"))
      (node (ref "SW1") (pin "E") (pinfunction "2_E") (pintype "passive"))
    )
    (net (code "84") (name "SCS_D3") (class "Default")
      (node (ref "STM32F407XX1") (pin "42") (pinfunction "PE11_42") (pintype "bidirectional"))
      (node (ref "SW1") (pin "B") (pinfunction "B_B") (pintype "passive"))
    )
    (net (code "85") (name "SCS_D4") (class "Default")
      (node (ref "STM32F407XX1") (pin "43") (pinfunction "PE12_43") (pintype "bidirectional"))
      (node (ref "SW1") (pin "A") (pinfunction "A_A") (pintype "passive"))
    )
    (net (code "86") (name "SCS_D5") (class "Default")
      (node (ref "STM32F407XX1") (pin "44") (pinfunction "PE13_44") (pintype "bidirectional"))
      (node (ref "SW2") (pin "E") (pinfunction "2_E") (pintype "passive"))
    )
    (net (code "87") (name "SCS_D6") (class "Default")
      (node (ref "R35") (pin "1") (pinfunction "1_1") (pintype "passive"))
      (node (ref "S2") (pin "3") (pinfunction "P_3") (pintype "passive"))
      (node (ref "S2") (pin "4") (pinfunction "P1_4") (pintype "passive"))
      (node (ref "STM32F407XX1") (pin "45") (pinfunction "PE14_45") (pintype "bidirectional"))
    )
    (net (code "88") (name "SCS_D7") (class "Default")
      (node (ref "R34") (pin "1") (pinfunction "1_1") (pintype "passive"))
      (node (ref "S1") (pin "3") (pinfunction "P_3") (pintype "passive"))
      (node (ref "S1") (pin "4") (pinfunction "P1_4") (pintype "passive"))
      (node (ref "STM32F407XX1") (pin "46") (pinfunction "PE15_46") (pintype "bidirectional"))
    )
    (net (code "89") (name "SCS_D8") (class "Default")
      (node (ref "R38") (pin "1") (pinfunction "1_1") (pintype "passive"))
      (node (ref "S5") (pin "3") (pinfunction "P_3") (pintype "passive"))
      (node (ref "S5") (pin "4") (pinfunction "P1_4") (pintype "passive"))
      (node (ref "STM32F407XX1") (pin "7") (pinfunction "PC13_7") (pintype "bidirectional"))
    )
    (net (code "90") (name "SCS_D9") (class "Default")
      (node (ref "R37") (pin "1") (pinfunction "1_1") (pintype "passive"))
      (node (ref "S4") (pin "3") (pinfunction "P_3") (pintype "passive"))
      (node (ref "S4") (pin "4") (pinfunction "P1_4") (pintype "passive"))
      (node (ref "STM32F407XX1") (pin "8") (pinfunction "PC14_8") (pintype "bidirectional"))
    )
    (net (code "91") (name "SCS_D10") (class "Default")
      (node (ref "R36") (pin "1") (pinfunction "1_1") (pintype "passive"))
      (node (ref "S3") (pin "3") (pinfunction "P_3") (pintype "passive"))
      (node (ref "S3") (pin "4") (pinfunction "P1_4") (pintype "passive"))
      (node (ref "STM32F407XX1") (pin "9") (pinfunction "PC15_9") (pintype "bidirectional"))
    )
    (net (code "92") (name "SDA") (class "Default")
      (node (ref "C27") (pin "2") (pinfunction "P$2_2") (pintype "passive"))
      (node (ref "R13") (pin "1") (pinfunction "1_1") (pintype "passive"))
      (node (ref "STM32F407XX1") (pin "48") (pinfunction "PB11_48") (pintype "bidirectional"))
      (node (ref "U1") (pin "5") (pinfunction "SDA_5") (pintype "bidirectional"))
    )
    (net (code "93") (name "SWCLK") (class "Default")
      (node (ref "R12") (pin "2") (pinfunction "2_2") (pintype "passive"))
      (node (ref "STM32F407XX1") (pin "76") (pinfunction "PA14_76") (pintype "bidirectional"))
    )
    (net (code "94") (name "SWDIO") (class "Default")
      (node (ref "R14") (pin "2") (pinfunction "2_2") (pintype "passive"))
      (node (ref "STM32F407XX1") (pin "72") (pinfunction "PA13_72") (pintype "bidirectional"))
    )
    (net (code "95") (name "SW_USER") (class "Default")
      (node (ref "R8") (pin "1") (pinfunction "1_1") (pintype "passive"))
      (node (ref "STM32F407XX1") (pin "23") (pinfunction "PA0_23") (pintype "bidirectional"))
    )
    (net (code "96") (name "USB_D_N") (class "Default")
      (node (ref "R6") (pin "2") (pinfunction "2_2") (pintype "passive"))
      (node (ref "STM32F407XX1") (pin "70") (pinfunction "PA11_70") (pintype "bidirectional"))
    )
    (net (code "97") (name "USB_D_PP") (class "Default")
      (node (ref "R7") (pin "2") (pinfunction "2_2") (pintype "passive"))
      (node (ref "STM32F407XX1") (pin "71") (pinfunction "PA12_71") (pintype "bidirectional"))
    )
    (net (code "98") (name "unconnected-(IC5A-QH*-Pad9)") (class "Default")
      (node (ref "IC5") (pin "9") (pinfunction "QH*_9") (pintype "tri_state"))
    )
    (net (code "99") (name "unconnected-(MIDI_IN1-Pad1)") (class "Default")
      (node (ref "MIDI_IN1") (pin "1") (pinfunction "1_1") (pintype "passive"))
    )
    (net (code "100") (name "unconnected-(MIDI_IN1-Pad2)") (class "Default")
      (node (ref "MIDI_IN1") (pin "2") (pinfunction "2_2") (pintype "passive"))
    )
    (net (code "101") (name "unconnected-(MIDI_IN1-Pad3)") (class "Default")
      (node (ref "MIDI_IN1") (pin "3") (pinfunction "3_3") (pintype "passive"))
    )
    (net (code "102") (name "unconnected-(MIDI_IN2-Pad1)") (class "Default")
      (node (ref "MIDI_IN2") (pin "1") (pinfunction "1_1") (pintype "passive"))
    )
    (net (code "103") (name "unconnected-(MIDI_IN2-Pad2)") (class "Default")
      (node (ref "MIDI_IN2") (pin "2") (pinfunction "2_2") (pintype "passive"))
    )
    (net (code "104") (name "unconnected-(MIDI_IN2-Pad3)") (class "Default")
      (node (ref "MIDI_IN2") (pin "3") (pinfunction "3_3") (pintype "passive"))
    )
    (net (code "105") (name "unconnected-(MIDI_OUT1-Pad1)") (class "Default")
      (node (ref "MIDI_OUT1") (pin "1") (pinfunction "1_1") (pintype "passive"))
    )
    (net (code "106") (name "unconnected-(MIDI_OUT1-Pad3)") (class "Default")
      (node (ref "MIDI_OUT1") (pin "3") (pinfunction "3_3") (pintype "passive"))
    )
    (net (code "107") (name "unconnected-(MIDI_OUT2-Pad1)") (class "Default")
      (node (ref "MIDI_OUT2") (pin "1") (pinfunction "1_1") (pintype "passive"))
    )
    (net (code "108") (name "unconnected-(MIDI_OUT2-Pad3)") (class "Default")
      (node (ref "MIDI_OUT2") (pin "3") (pinfunction "3_3") (pintype "passive"))
    )
    (net (code "109") (name "unconnected-(STM32F407XX1-PA5-Pad30)") (class "Default")
      (node (ref "STM32F407XX1") (pin "30") (pinfunction "PA5_30") (pintype "bidirectional"))
    )
    (net (code "110") (name "unconnected-(STM32F407XX1-PA6-Pad31)") (class "Default")
      (node (ref "STM32F407XX1") (pin "31") (pinfunction "PA6_31") (pintype "bidirectional"))
    )
    (net (code "111") (name "unconnected-(STM32F407XX1-PA7-Pad32)") (class "Default")
      (node (ref "STM32F407XX1") (pin "32") (pinfunction "PA7_32") (pintype "bidirectional"))
    )
    (net (code "112") (name "unconnected-(STM32F407XX1-PA10-Pad69)") (class "Default")
      (node (ref "STM32F407XX1") (pin "69") (pinfunction "PA10_69") (pintype "bidirectional"))
    )
    (net (code "113") (name "unconnected-(STM32F407XX1-PB0-Pad35)") (class "Default")
      (node (ref "STM32F407XX1") (pin "35") (pinfunction "PB0_35") (pintype "bidirectional"))
    )
    (net (code "114") (name "unconnected-(STM32F407XX1-PB1-Pad36)") (class "Default")
      (node (ref "STM32F407XX1") (pin "36") (pinfunction "PB1_36") (pintype "bidirectional"))
    )
    (net (code "115") (name "unconnected-(STM32F407XX1-PB6-Pad92)") (class "Default")
      (node (ref "STM32F407XX1") (pin "92") (pinfunction "PB6_92") (pintype "bidirectional"))
    )
    (net (code "116") (name "unconnected-(STM32F407XX1-PB7-Pad93)") (class "Default")
      (node (ref "STM32F407XX1") (pin "93") (pinfunction "PB7_93") (pintype "bidirectional"))
    )
    (net (code "117") (name "unconnected-(STM32F407XX1-PB9-Pad96)") (class "Default")
      (node (ref "STM32F407XX1") (pin "96") (pinfunction "PB9_96") (pintype "bidirectional"))
    )
    (net (code "118") (name "unconnected-(STM32F407XX1-PC5-Pad34)") (class "Default")
      (node (ref "STM32F407XX1") (pin "34") (pinfunction "PC5_34") (pintype "bidirectional"))
    )
    (net (code "119") (name "unconnected-(STM32F407XX1-PC6-Pad63)") (class "Default")
      (node (ref "STM32F407XX1") (pin "63") (pinfunction "PC6_63") (pintype "bidirectional"))
    )
    (net (code "120") (name "unconnected-(STM32F407XX1-PC7-Pad64)") (class "Default")
      (node (ref "STM32F407XX1") (pin "64") (pinfunction "PC7_64") (pintype "bidirectional"))
    )
    (net (code "121") (name "unconnected-(STM32F407XX1-PC9-Pad66)") (class "Default")
      (node (ref "STM32F407XX1") (pin "66") (pinfunction "PC9_66") (pintype "bidirectional"))
    )
    (net (code "122") (name "unconnected-(STM32F407XX1-PC10-Pad78)") (class "Default")
      (node (ref "STM32F407XX1") (pin "78") (pinfunction "PC10_78") (pintype "bidirectional"))
    )
    (net (code "123") (name "unconnected-(STM32F407XX1-PC12-Pad80)") (class "Default")
      (node (ref "STM32F407XX1") (pin "80") (pinfunction "PC12_80") (pintype "bidirectional"))
    )
    (net (code "124") (name "unconnected-(STM32F407XX1-PD0-Pad81)") (class "Default")
      (node (ref "STM32F407XX1") (pin "81") (pinfunction "PD0_81") (pintype "bidirectional"))
    )
    (net (code "125") (name "unconnected-(STM32F407XX1-PD1-Pad82)") (class "Default")
      (node (ref "STM32F407XX1") (pin "82") (pinfunction "PD1_82") (pintype "bidirectional"))
    )
    (net (code "126") (name "unconnected-(STM32F407XX1-PD2-Pad83)") (class "Default")
      (node (ref "STM32F407XX1") (pin "83") (pinfunction "PD2_83") (pintype "bidirectional"))
    )
    (net (code "127") (name "unconnected-(STM32F407XX1-PD4-Pad85)") (class "Default")
      (node (ref "STM32F407XX1") (pin "85") (pinfunction "PD4_85") (pintype "bidirectional"))
    )
    (net (code "128") (name "unconnected-(STM32F407XX1-PD5-Pad86)") (class "Default")
      (node (ref "STM32F407XX1") (pin "86") (pinfunction "PD5_86") (pintype "bidirectional"))
    )
    (net (code "129") (name "unconnected-(STM32F407XX1-PD11-Pad58)") (class "Default")
      (node (ref "STM32F407XX1") (pin "58") (pinfunction "PD11_58") (pintype "bidirectional"))
    )
    (net (code "130") (name "unconnected-(STM32F407XX1-PD14-Pad61)") (class "Default")
      (node (ref "STM32F407XX1") (pin "61") (pinfunction "PD14_61") (pintype "bidirectional"))
    )
    (net (code "131") (name "unconnected-(STM32F407XX1-PD15-Pad62)") (class "Default")
      (node (ref "STM32F407XX1") (pin "62") (pinfunction "PD15_62") (pintype "bidirectional"))
    )
    (net (code "132") (name "unconnected-(STM32F407XX1-PE0-Pad97)") (class "Default")
      (node (ref "STM32F407XX1") (pin "97") (pinfunction "PE0_97") (pintype "bidirectional"))
    )
    (net (code "133") (name "unconnected-(STM32F407XX1-PE1-Pad98)") (class "Default")
      (node (ref "STM32F407XX1") (pin "98") (pinfunction "PE1_98") (pintype "bidirectional"))
    )
    (net (code "134") (name "unconnected-(STM32F407XX1-PE2-Pad1)") (class "Default")
      (node (ref "STM32F407XX1") (pin "1") (pinfunction "PE2_1") (pintype "bidirectional"))
    )
    (net (code "135") (name "unconnected-(STM32F407XX1-PE3-Pad2)") (class "Default")
      (node (ref "STM32F407XX1") (pin "2") (pinfunction "PE3_2") (pintype "bidirectional"))
    )
    (net (code "136") (name "unconnected-(STM32F407XX1-PE4-Pad3)") (class "Default")
      (node (ref "STM32F407XX1") (pin "3") (pinfunction "PE4_3") (pintype "bidirectional"))
    )
    (net (code "137") (name "unconnected-(STM32F407XX1-PE6-Pad5)") (class "Default")
      (node (ref "STM32F407XX1") (pin "5") (pinfunction "PE6_5") (pintype "bidirectional"))
    )
    (net (code "138") (name "unconnected-(STM32F407XX1-PE7-Pad38)") (class "Default")
      (node (ref "STM32F407XX1") (pin "38") (pinfunction "PE7_38") (pintype "bidirectional"))
    )
  )
)
